# geyser-001.net
KiCad netlist of a schematic drawn in EAGLE
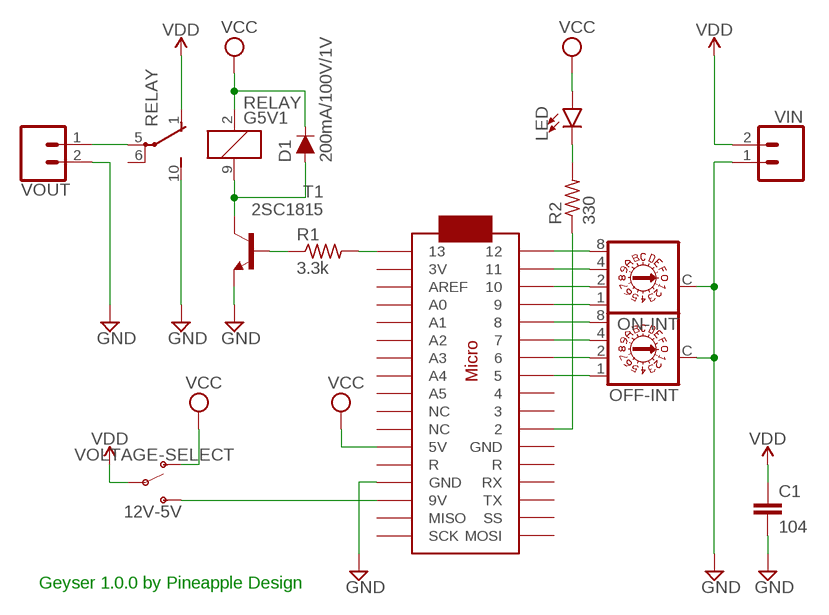
[diagram p0: schematic, sheet 1]

(export (version "E")
  (design (tool "Eeschema 10.0.6"))
  (components
    (comp (ref "C1")
      (value "104")
      (footprint "eagle-import:C2.5-3")
      (libsource (lib "eagle-import") (part "C2,5-3"))
    )
    (comp (ref "D1")
      (value "200mA/100V/1V")
      (footprint "eagle-import:DIODE-1N4148")
      (libsource (lib "eagle-import") (part "DIODE-1N4148"))
    )
    (comp (ref "LED")
      (value "LED-3MM-NO_SILK")
      (footprint "eagle-import:LED_3MM-NS")
      (libsource (lib "eagle-import") (part "LED-3MM-NO_SILK"))
    )
    (comp (ref "OFF-INT")
      (value "A1353HEX")
      (footprint "eagle-import:A1353HEX")
      (libsource (lib "eagle-import") (part "A1353HEX"))
    )
    (comp (ref "ON-INT")
      (value "A1353HEX")
      (footprint "eagle-import:A1353HEX")
      (libsource (lib "eagle-import") (part "A1353HEX"))
    )
    (comp (ref "R1")
      (value "3.3k")
      (footprint "eagle-import:0204_5")
      (libsource (lib "eagle-import") (part "R-US_0204/5"))
    )
    (comp (ref "R2")
      (value "330")
      (footprint "eagle-import:0204_5")
      (libsource (lib "eagle-import") (part "R-US_0204/5"))
    )
    (comp (ref "RELAY")
      (value "G5V1")
      (footprint "eagle-import:G5V1")
      (fields (field (name "MPN") "G5V-1-DC24"))
      (libsource (lib "eagle-import") (part "G5V1"))
    )
    (comp (ref "T1")
      (value "2SC1815")
      (footprint "eagle-import:TO92-ECB")
      (libsource (lib "eagle-import") (part "2SC1815"))
    )
    (comp (ref "U$1")
      (value "ARDUINOMICRO")
      (footprint "eagle-import:ARDUINOMICRO")
      (libsource (lib "eagle-import") (part "ARDUINOMICRO"))
    )
    (comp (ref "VIN")
      (value "CONN_02JST-PTH-2")
      (footprint "eagle-import:JST-2-PTH")
      (libsource (lib "eagle-import") (part "CONN_02JST-PTH-2"))
    )
    (comp (ref "VOLTAGE-SELECT")
      (value "12V-5V")
      (footprint "eagle-import:SWITCH_SPDT_PTH_11.6X4.0MM")
      (libsource (lib "eagle-import") (part "SWITCH-SPDT-PTH-11.6X4.0MM"))
    )
    (comp (ref "VOUT")
      (value "CONN_02JST-PTH-2")
      (footprint "eagle-import:JST-2-PTH")
      (libsource (lib "eagle-import") (part "CONN_02JST-PTH-2"))
    )
  )
  (nets
    (net (code "1") (name "GND") (class "Default")
      (node (ref "C1") (pin "2") (pinfunction "2_2") (pintype "passive"))
      (node (ref "OFF-INT") (pin "C") (pinfunction "C_C") (pintype "passive"))
      (node (ref "ON-INT") (pin "C") (pinfunction "C_C") (pintype "passive"))
      (node (ref "RELAY") (pin "10") (pinfunction "S_10") (pintype "passive"))
      (node (ref "T1") (pin "E") (pinfunction "E_E") (pintype "passive"))
      (node (ref "U$1") (pin "P$12") (pinfunction "GND_P$12") (pintype "bidirectional"))
      (node (ref "VIN") (pin "1") (pinfunction "1_1") (pintype "passive"))
      (node (ref "VOUT") (pin "2") (pinfunction "2_2") (pintype "passive"))
    )
    (net (code "2") (name "Net-(LED-C)") (class "Default")
      (node (ref "LED") (pin "K") (pinfunction "C_K") (pintype "passive"))
      (node (ref "R2") (pin "2") (pinfunction "2_2") (pintype "passive"))
    )
    (net (code "3") (name "Net-(R1-Pad1)") (class "Default")
      (node (ref "R1") (pin "1") (pinfunction "1_1") (pintype "passive"))
      (node (ref "T1") (pin "B") (pinfunction "B_B") (pintype "passive"))
    )
    (net (code "4") (name "Net-(RELAYA-2)") (class "Default")
      (node (ref "D1") (pin "A") (pinfunction "A_A") (pintype "passive"))
      (node (ref "RELAY") (pin "9") (pinfunction "2_9") (pintype "passive"))
      (node (ref "T1") (pin "C") (pinfunction "C_C") (pintype "passive"))
    )
    (net (code "5") (name "Net-(RELAYB-P-Pad5)") (class "Default")
      (node (ref "RELAY") (pin "5") (pinfunction "P_5") (pintype "passive"))
      (node (ref "VOUT") (pin "1") (pinfunction "1_1") (pintype "passive"))
    )
    (net (code "6") (name "Net-(U$1-2)") (class "Default")
      (node (ref "R2") (pin "1") (pinfunction "1_1") (pintype "passive"))
      (node (ref "U$1") (pin "P$11") (pinfunction "2_P$11") (pintype "bidirectional"))
    )
    (net (code "7") (name "Net-(U$1-5)") (class "Default")
      (node (ref "OFF-INT") (pin "1") (pinfunction "1_1") (pintype "passive"))
      (node (ref "U$1") (pin "P$8") (pinfunction "5_P$8") (pintype "bidirectional"))
    )
    (net (code "8") (name "Net-(U$1-6)") (class "Default")
      (node (ref "OFF-INT") (pin "2") (pinfunction "2_2") (pintype "passive"))
      (node (ref "U$1") (pin "P$7") (pinfunction "6_P$7") (pintype "bidirectional"))
    )
    (net (code "9") (name "Net-(U$1-7)") (class "Default")
      (node (ref "OFF-INT") (pin "4") (pinfunction "4_4") (pintype "passive"))
      (node (ref "U$1") (pin "P$6") (pinfunction "7_P$6") (pintype "bidirectional"))
    )
    (net (code "10") (name "Net-(U$1-8)") (class "Default")
      (node (ref "OFF-INT") (pin "8") (pinfunction "8_8") (pintype "passive"))
      (node (ref "U$1") (pin "P$5") (pinfunction "8_P$5") (pintype "bidirectional"))
    )
    (net (code "11") (name "Net-(U$1-9)") (class "Default")
      (node (ref "ON-INT") (pin "1") (pinfunction "1_1") (pintype "passive"))
      (node (ref "U$1") (pin "P$4") (pinfunction "9_P$4") (pintype "bidirectional"))
    )
    (net (code "12") (name "Net-(U$1-9V)") (class "Default")
      (node (ref "U$1") (pin "P$20") (pinfunction "9V_P$20") (pintype "bidirectional"))
      (node (ref "VOLTAGE-SELECT") (pin "3") (pinfunction "S_3") (pintype "passive"))
    )
    (net (code "13") (name "Net-(U$1-10)") (class "Default")
      (node (ref "ON-INT") (pin "2") (pinfunction "2_2") (pintype "passive"))
      (node (ref "U$1") (pin "P$3") (pinfunction "10_P$3") (pintype "bidirectional"))
    )
    (net (code "14") (name "Net-(U$1-11)") (class "Default")
      (node (ref "ON-INT") (pin "4") (pinfunction "4_4") (pintype "passive"))
      (node (ref "U$1") (pin "P$2") (pinfunction "11_P$2") (pintype "bidirectional"))
    )
    (net (code "15") (name "Net-(U$1-12)") (class "Default")
      (node (ref "ON-INT") (pin "8") (pinfunction "8_8") (pintype "passive"))
      (node (ref "U$1") (pin "P$1") (pinfunction "12_P$1") (pintype "bidirectional"))
    )
    (net (code "16") (name "Net-(U$1-13)") (class "Default")
      (node (ref "R1") (pin "2") (pinfunction "2_2") (pintype "passive"))
      (node (ref "U$1") (pin "P$34") (pinfunction "13_P$34") (pintype "bidirectional"))
    )
    (net (code "17") (name "VCC") (class "Default")
      (node (ref "D1") (pin "C") (pinfunction "C_C") (pintype "passive"))
      (node (ref "LED") (pin "A") (pinfunction "A_A") (pintype "passive"))
      (node (ref "RELAY") (pin "2") (pinfunction "1_2") (pintype "passive"))
      (node (ref "U$1") (pin "P$23") (pinfunction "5V_P$23") (pintype "bidirectional"))
      (node (ref "VOLTAGE-SELECT") (pin "1") (pinfunction "O_1") (pintype "passive"))
    )
    (net (code "18") (name "VDD") (class "Default")
      (node (ref "C1") (pin "1") (pinfunction "1_1") (pintype "passive"))
      (node (ref "RELAY") (pin "1") (pinfunction "O_1") (pintype "passive"))
      (node (ref "VIN") (pin "2") (pinfunction "2_2") (pintype "passive"))
      (node (ref "VOLTAGE-SELECT") (pin "2") (pinfunction "P_2") (pintype "passive"))
    )
    (net (code "19") (name "unconnected-(RELAYB-P-Pad6)") (class "Default")
      (node (ref "RELAY") (pin "6") (pinfunction "P_6") (pintype "passive"))
    )
    (net (code "20") (name "unconnected-(U$1-3-PadP$10)") (class "Default")
      (node (ref "U$1") (pin "P$10") (pinfunction "3_P$10") (pintype "bidirectional"))
    )
    (net (code "21") (name "unconnected-(U$1-3V-PadP$33)") (class "Default")
      (node (ref "U$1") (pin "P$33") (pinfunction "3V_P$33") (pintype "bidirectional"))
    )
    (net (code "22") (name "unconnected-(U$1-4-PadP$9)") (class "Default")
      (node (ref "U$1") (pin "P$9") (pinfunction "4_P$9") (pintype "bidirectional"))
    )
    (net (code "23") (name "unconnected-(U$1-A0-PadP$31)") (class "Default")
      (node (ref "U$1") (pin "P$31") (pinfunction "A0_P$31") (pintype "bidirectional"))
    )
    (net (code "24") (name "unconnected-(U$1-A1-PadP$30)") (class "Default")
      (node (ref "U$1") (pin "P$30") (pinfunction "A1_P$30") (pintype "bidirectional"))
    )
    (net (code "25") (name "unconnected-(U$1-A2-PadP$29)") (class "Default")
      (node (ref "U$1") (pin "P$29") (pinfunction "A2_P$29") (pintype "bidirectional"))
    )
    (net (code "26") (name "unconnected-(U$1-A3-PadP$28)") (class "Default")
      (node (ref "U$1") (pin "P$28") (pinfunction "A3_P$28") (pintype "bidirectional"))
    )
    (net (code "27") (name "unconnected-(U$1-A4-PadP$27)") (class "Default")
      (node (ref "U$1") (pin "P$27") (pinfunction "A4_P$27") (pintype "bidirectional"))
    )
    (net (code "28") (name "unconnected-(U$1-A5-PadP$26)") (class "Default")
      (node (ref "U$1") (pin "P$26") (pinfunction "A5_P$26") (pintype "bidirectional"))
    )
    (net (code "29") (name "unconnected-(U$1-AREF-PadP$32)") (class "Default")
      (node (ref "U$1") (pin "P$32") (pinfunction "AREF_P$32") (pintype "bidirectional"))
    )
    (net (code "30") (name "unconnected-(U$1-GND-PadP$21)") (class "Default")
      (node (ref "U$1") (pin "P$21") (pinfunction "GND_P$21") (pintype "bidirectional"))
    )
    (net (code "31") (name "unconnected-(U$1-MISO-PadP$19)") (class "Default")
      (node (ref "U$1") (pin "P$19") (pinfunction "MISO_P$19") (pintype "bidirectional"))
    )
    (net (code "32") (name "unconnected-(U$1-MOSI-PadP$17)") (class "Default")
      (node (ref "U$1") (pin "P$17") (pinfunction "MOSI_P$17") (pintype "bidirectional"))
    )
    (net (code "33") (name "unconnected-(U$1-NC-PadP$24)") (class "Default")
      (node (ref "U$1") (pin "P$24") (pinfunction "NC_P$24") (pintype "bidirectional"))
    )
    (net (code "34") (name "unconnected-(U$1-NC-PadP$25)") (class "Default")
      (node (ref "U$1") (pin "P$25") (pinfunction "NC_P$25") (pintype "bidirectional"))
    )
    (net (code "35") (name "unconnected-(U$1-R-PadP$13)") (class "Default")
      (node (ref "U$1") (pin "P$13") (pinfunction "R_P$13") (pintype "bidirectional"))
    )
    (net (code "36") (name "unconnected-(U$1-R-PadP$22)") (class "Default")
      (node (ref "U$1") (pin "P$22") (pinfunction "R_P$22") (pintype "bidirectional"))
    )
    (net (code "37") (name "unconnected-(U$1-RX-PadP$14)") (class "Default")
      (node (ref "U$1") (pin "P$14") (pinfunction "RX_P$14") (pintype "bidirectional"))
    )
    (net (code "38") (name "unconnected-(U$1-SCK-PadP$18)") (class "Default")
      (node (ref "U$1") (pin "P$18") (pinfunction "SCK_P$18") (pintype "bidirectional"))
    )
    (net (code "39") (name "unconnected-(U$1-SS-PadP$16)") (class "Default")
      (node (ref "U$1") (pin "P$16") (pinfunction "SS_P$16") (pintype "bidirectional"))
    )
    (net (code "40") (name "unconnected-(U$1-TX-PadP$15)") (class "Default")
      (node (ref "U$1") (pin "P$15") (pinfunction "TX_P$15") (pintype "bidirectional"))
    )
  )
)
